# extruder_breakout_14.net
KiCad netlist of a schematic drawn in EAGLE
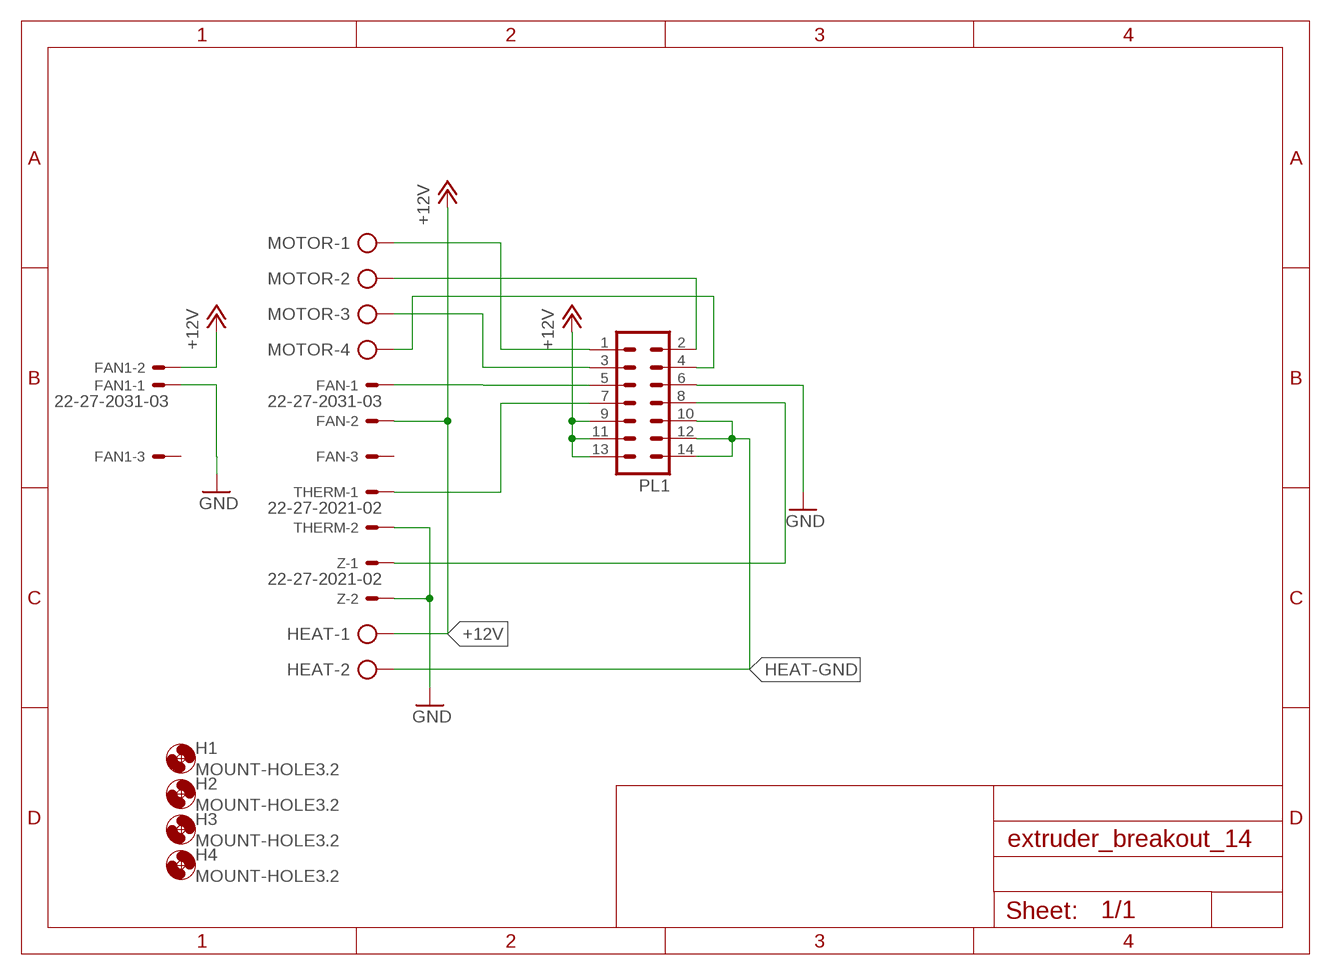
[diagram p0: schematic, sheet 1]

(export (version "E")
  (design (tool "Eeschema 10.0.6"))
  (components
    (comp (ref "FAN")
      (value "22-27-2031-03")
      (footprint "eagle-import:6410-03")
      (libsource (lib "eagle-import") (part "22-?-0327-2031"))
    )
    (comp (ref "FAN1")
      (value "22-27-2031-03")
      (footprint "eagle-import:6410-03")
      (libsource (lib "eagle-import") (part "22-?-0327-2031"))
    )
    (comp (ref "H1")
      (value "MOUNT-HOLE3.2")
      (footprint "eagle-import:3,2")
      (libsource (lib "eagle-import") (part "MOUNT-HOLE3.2"))
    )
    (comp (ref "H2")
      (value "MOUNT-HOLE3.2")
      (footprint "eagle-import:3,2")
      (libsource (lib "eagle-import") (part "MOUNT-HOLE3.2"))
    )
    (comp (ref "H3")
      (value "MOUNT-HOLE3.2")
      (footprint "eagle-import:3,2")
      (libsource (lib "eagle-import") (part "MOUNT-HOLE3.2"))
    )
    (comp (ref "H4")
      (value "MOUNT-HOLE3.2")
      (footprint "eagle-import:3,2")
      (libsource (lib "eagle-import") (part "MOUNT-HOLE3.2"))
    )
    (comp (ref "HEAT")
      (value "AK500/2")
      (footprint "eagle-import:AK500_2")
      (libsource (lib "eagle-import") (part "AK500/2"))
    )
    (comp (ref "MOTOR")
      (value "AK500/4")
      (footprint "eagle-import:AK500_4")
      (libsource (lib "eagle-import") (part "AK500/4"))
    )
    (comp (ref "PL1")
      (value "14V")
      (footprint "eagle-import:14V")
      (libsource (lib "eagle-import") (part "14V"))
    )
    (comp (ref "THERM")
      (value "22-27-2021-02")
      (footprint "eagle-import:6410-02")
      (libsource (lib "eagle-import") (part "22-?-0227-2021"))
    )
    (comp (ref "Z")
      (value "22-27-2021-02")
      (footprint "eagle-import:6410-02")
      (libsource (lib "eagle-import") (part "22-?-0227-2021"))
    )
  )
  (nets
    (net (code "1") (name "+12V") (class "Default")
      (node (ref "FAN") (pin "2") (pinfunction "S_2") (pintype "passive"))
      (node (ref "FAN1") (pin "2") (pinfunction "S_2") (pintype "passive"))
      (node (ref "HEAT") (pin "1") (pinfunction "KL_1") (pintype "passive"))
      (node (ref "PL1") (pin "11") (pinfunction "11_11") (pintype "passive"))
      (node (ref "PL1") (pin "13") (pinfunction "13_13") (pintype "passive"))
      (node (ref "PL1") (pin "9") (pinfunction "9_9") (pintype "passive"))
    )
    (net (code "2") (name "GND") (class "Default")
      (node (ref "FAN1") (pin "1") (pinfunction "S_1") (pintype "passive"))
      (node (ref "PL1") (pin "6") (pinfunction "6_6") (pintype "passive"))
      (node (ref "THERM") (pin "2") (pinfunction "S_2") (pintype "passive"))
      (node (ref "Z") (pin "2") (pinfunction "S_2") (pintype "passive"))
    )
    (net (code "3") (name "HEAT-GND") (class "Default")
      (node (ref "HEAT") (pin "2") (pinfunction "KL_2") (pintype "passive"))
      (node (ref "PL1") (pin "10") (pinfunction "10_10") (pintype "passive"))
      (node (ref "PL1") (pin "12") (pinfunction "12_12") (pintype "passive"))
      (node (ref "PL1") (pin "14") (pinfunction "14_14") (pintype "passive"))
    )
    (net (code "4") (name "Net-(FANA-S)") (class "Default")
      (node (ref "FAN") (pin "1") (pinfunction "S_1") (pintype "passive"))
      (node (ref "PL1") (pin "5") (pinfunction "5_5") (pintype "passive"))
    )
    (net (code "5") (name "Net-(MOTORA-KL)") (class "Default")
      (node (ref "MOTOR") (pin "1") (pinfunction "KL_1") (pintype "passive"))
      (node (ref "PL1") (pin "1") (pinfunction "1_1") (pintype "passive"))
    )
    (net (code "6") (name "Net-(MOTORB-KL)") (class "Default")
      (node (ref "MOTOR") (pin "2") (pinfunction "KL_2") (pintype "passive"))
      (node (ref "PL1") (pin "2") (pinfunction "2_2") (pintype "passive"))
    )
    (net (code "7") (name "Net-(MOTORC-KL)") (class "Default")
      (node (ref "MOTOR") (pin "3") (pinfunction "KL_3") (pintype "passive"))
      (node (ref "PL1") (pin "3") (pinfunction "3_3") (pintype "passive"))
    )
    (net (code "8") (name "Net-(MOTORD-KL)") (class "Default")
      (node (ref "MOTOR") (pin "4") (pinfunction "KL_4") (pintype "passive"))
      (node (ref "PL1") (pin "4") (pinfunction "4_4") (pintype "passive"))
    )
    (net (code "9") (name "Net-(THERMA-S)") (class "Default")
      (node (ref "PL1") (pin "7") (pinfunction "7_7") (pintype "passive"))
      (node (ref "THERM") (pin "1") (pinfunction "S_1") (pintype "passive"))
    )
    (net (code "10") (name "Net-(ZA-S)") (class "Default")
      (node (ref "PL1") (pin "8") (pinfunction "8_8") (pintype "passive"))
      (node (ref "Z") (pin "1") (pinfunction "S_1") (pintype "passive"))
    )
    (net (code "11") (name "unconnected-(FAN1C-S-Pad3)") (class "Default")
      (node (ref "FAN1") (pin "3") (pinfunction "S_3") (pintype "passive"))
    )
    (net (code "12") (name "unconnected-(FANC-S-Pad3)") (class "Default")
      (node (ref "FAN") (pin "3") (pinfunction "S_3") (pintype "passive"))
    )
  )
)
